# usb2uart_ch340.net
KiCad netlist of a schematic drawn in Altium Designer
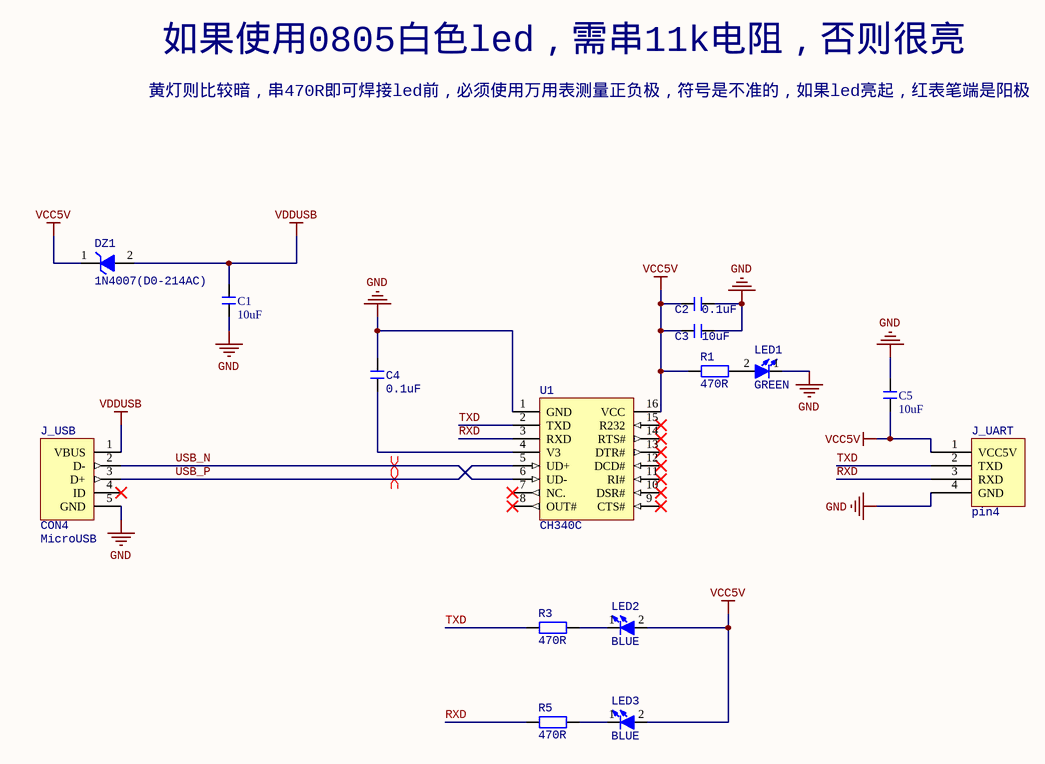
[diagram p0: usb2uart_ch340.SchDoc]

(export (version "E")
  (design (tool "Eeschema 10.0.6"))
  (components
    (comp (ref "C1")
      (value "10uF")
      (footprint "C 0603_M")
      (description "无极性贴片电容")
      (fields (field (name "版权归属") "源创客"))
      (libsource (lib "usb2uart_ch340") (part "C"))
    )
    (comp (ref "C2")
      (value "0.1uF")
      (footprint "C 0402_M")
      (description "无极性贴片电容")
      (fields (field (name "版权归属") "源创客"))
      (libsource (lib "usb2uart_ch340") (part "C"))
    )
    (comp (ref "C3")
      (value "10uF")
      (footprint "C 0603_M")
      (description "无极性贴片电容")
      (fields (field (name "版权归属") "源创客"))
      (libsource (lib "usb2uart_ch340") (part "C"))
    )
    (comp (ref "C4")
      (value "0.1uF")
      (footprint "C 0402_M")
      (description "无极性贴片电容")
      (fields (field (name "版权归属") "源创客"))
      (libsource (lib "usb2uart_ch340") (part "C"))
    )
    (comp (ref "C5")
      (value "10uF")
      (footprint "C 0603_M")
      (description "无极性贴片电容")
      (fields (field (name "版权归属") "源创客"))
      (libsource (lib "usb2uart_ch340") (part "C"))
    )
    (comp (ref "DZ1")
      (value "1N4007(D0-214AC)")
      (footprint "D SMA(DO-214AC)")
      (description "稳压二极管")
      (fields (field (name "版权归属") "源创客"))
      (libsource (lib "Schlib1") (part "DZ"))
    )
    (comp (ref "J_UART")
      (value "pin4")
      (footprint "HDR2.54-LI-4P")
      (libsource (lib "usb2uart_ch340") (part "pin4"))
    )
    (comp (ref "J_USB")
      (value "CON4")
      (footprint "MicroUsb_C404969")
      (libsource (lib "Schlib1") (part "MicroUSB_5P"))
    )
    (comp (ref "LED1")
      (value "GREEN")
      (footprint "D 0805 led")
      (description "贴片LED")
      (fields (field (name "版权归属") "源创客"))
      (libsource (lib "usb2uart_ch340") (part "D LED-SMD"))
    )
    (comp (ref "LED2")
      (value "BLUE")
      (footprint "D 0805 led")
      (description "贴片LED")
      (fields (field (name "版权归属") "源创客"))
      (libsource (lib "usb2uart_ch340") (part "D LED-SMD"))
    )
    (comp (ref "LED3")
      (value "BLUE")
      (footprint "D 0805 led")
      (description "贴片LED")
      (fields (field (name "版权归属") "源创客"))
      (libsource (lib "usb2uart_ch340") (part "D LED-SMD"))
    )
    (comp (ref "R1")
      (value "470R")
      (footprint "R 0603C")
      (description "贴片电阻")
      (libsource (lib "usb2uart_ch340") (part "R"))
    )
    (comp (ref "R3")
      (value "470R")
      (footprint "R 0603C")
      (description "贴片电阻")
      (libsource (lib "usb2uart_ch340") (part "R"))
    )
    (comp (ref "R5")
      (value "470R")
      (footprint "R 0603C")
      (description "贴片电阻")
      (libsource (lib "usb2uart_ch340") (part "R"))
    )
    (comp (ref "U1")
      (value "CH340C")
      (footprint "SOP-16_150mil")
      (description "CH340 是一个 USB 总线的转接芯片，实现 USB 转串口或者 USB 转打印口。")
      (libsource (lib "usb2uart_ch340") (part "CH340C"))
    )
  )
  (nets
    (net (code "1") (name "/RXD") (class "Default")
      (node (ref "J_UART") (pin "3") (pinfunction "RXD_3") (pintype "passive"))
      (node (ref "R5") (pin "1") (pinfunction "1_1") (pintype "passive"))
      (node (ref "U1") (pin "3") (pinfunction "RXD_3") (pintype "passive"))
    )
    (net (code "2") (name "/TXD") (class "Default")
      (node (ref "J_UART") (pin "2") (pinfunction "TXD_2") (pintype "passive"))
      (node (ref "R3") (pin "1") (pinfunction "1_1") (pintype "passive"))
      (node (ref "U1") (pin "2") (pinfunction "TXD_2") (pintype "passive"))
    )
    (net (code "3") (name "/USB_N") (class "Default")
      (node (ref "J_USB") (pin "2") (pinfunction "D-_2") (pintype "output"))
      (node (ref "U1") (pin "6") (pinfunction "UD-_6") (pintype "input"))
    )
    (net (code "4") (name "/USB_P") (class "Default")
      (node (ref "J_USB") (pin "3") (pinfunction "D+_3") (pintype "output"))
      (node (ref "U1") (pin "5") (pinfunction "UD+_5") (pintype "input"))
    )
    (net (code "5") (name "GND") (class "Default")
      (node (ref "C1") (pin "1") (pinfunction "1_1") (pintype "passive"))
      (node (ref "C2") (pin "2") (pinfunction "2_2") (pintype "passive"))
      (node (ref "C3") (pin "2") (pinfunction "2_2") (pintype "passive"))
      (node (ref "C4") (pin "2") (pinfunction "2_2") (pintype "passive"))
      (node (ref "C5") (pin "2") (pinfunction "2_2") (pintype "passive"))
      (node (ref "J_UART") (pin "4") (pinfunction "GND_4") (pintype "passive"))
      (node (ref "J_USB") (pin "5") (pinfunction "GND_5") (pintype "power_in"))
      (node (ref "LED1") (pin "1") (pinfunction "K_1") (pintype "passive"))
      (node (ref "U1") (pin "1") (pinfunction "GND_1") (pintype "power_in"))
    )
    (net (code "6") (name "Net-(LED1-A)") (class "Default")
      (node (ref "LED1") (pin "2") (pinfunction "A_2") (pintype "passive"))
      (node (ref "R1") (pin "2") (pinfunction "2_2") (pintype "passive"))
    )
    (net (code "7") (name "Net-(LED2-K)") (class "Default")
      (node (ref "LED2") (pin "1") (pinfunction "K_1") (pintype "passive"))
      (node (ref "R3") (pin "2") (pinfunction "2_2") (pintype "passive"))
    )
    (net (code "8") (name "Net-(LED3-K)") (class "Default")
      (node (ref "LED3") (pin "1") (pinfunction "K_1") (pintype "passive"))
      (node (ref "R5") (pin "2") (pinfunction "2_2") (pintype "passive"))
    )
    (net (code "9") (name "Net-(U1-V3)") (class "Default")
      (node (ref "C4") (pin "1") (pinfunction "1_1") (pintype "passive"))
      (node (ref "U1") (pin "4") (pinfunction "V3_4") (pintype "power_in"))
    )
    (net (code "10") (name "VCC5V") (class "Default")
      (node (ref "C2") (pin "1") (pinfunction "1_1") (pintype "passive"))
      (node (ref "C3") (pin "1") (pinfunction "1_1") (pintype "passive"))
      (node (ref "C5") (pin "1") (pinfunction "1_1") (pintype "passive"))
      (node (ref "DZ1") (pin "1") (pinfunction "K_1") (pintype "passive"))
      (node (ref "J_UART") (pin "1") (pinfunction "VCC5V_1") (pintype "passive"))
      (node (ref "LED2") (pin "2") (pinfunction "A_2") (pintype "passive"))
      (node (ref "LED3") (pin "2") (pinfunction "A_2") (pintype "passive"))
      (node (ref "R1") (pin "1") (pinfunction "1_1") (pintype "passive"))
      (node (ref "U1") (pin "16") (pinfunction "VCC_16") (pintype "power_in"))
    )
    (net (code "11") (name "VDDUSB") (class "Default")
      (node (ref "C1") (pin "2") (pinfunction "2_2") (pintype "passive"))
      (node (ref "DZ1") (pin "2") (pinfunction "A_2") (pintype "passive"))
      (node (ref "J_USB") (pin "1") (pinfunction "VBUS_1") (pintype "power_in"))
    )
    (net (code "12") (name "unconnected-(J_USB-ID-Pad4)") (class "Default")
      (node (ref "J_USB") (pin "4") (pinfunction "ID_4") (pintype "passive+no_connect"))
    )
    (net (code "13") (name "unconnected-(U1-CTS#-Pad9)") (class "Default")
      (node (ref "U1") (pin "9") (pinfunction "CTS#_9") (pintype "input+no_connect"))
    )
    (net (code "14") (name "unconnected-(U1-DCD#-Pad12)") (class "Default")
      (node (ref "U1") (pin "12") (pinfunction "DCD#_12") (pintype "input+no_connect"))
    )
    (net (code "15") (name "unconnected-(U1-DSR#-Pad10)") (class "Default")
      (node (ref "U1") (pin "10") (pinfunction "DSR#_10") (pintype "input+no_connect"))
    )
    (net (code "16") (name "unconnected-(U1-DTR#-Pad13)") (class "Default")
      (node (ref "U1") (pin "13") (pinfunction "DTR#_13") (pintype "output+no_connect"))
    )
    (net (code "17") (name "unconnected-(U1-NC.-Pad7)") (class "Default")
      (node (ref "U1") (pin "7") (pinfunction "NC._7") (pintype "output+no_connect"))
    )
    (net (code "18") (name "unconnected-(U1-OUT#-Pad8)") (class "Default")
      (node (ref "U1") (pin "8") (pinfunction "OUT#_8") (pintype "output+no_connect"))
    )
    (net (code "19") (name "unconnected-(U1-R232-Pad15)") (class "Default")
      (node (ref "U1") (pin "15") (pinfunction "R232_15") (pintype "input+no_connect"))
    )
    (net (code "20") (name "unconnected-(U1-RI#-Pad11)") (class "Default")
      (node (ref "U1") (pin "11") (pinfunction "RI#_11") (pintype "input+no_connect"))
    )
    (net (code "21") (name "unconnected-(U1-RTS#-Pad14)") (class "Default")
      (node (ref "U1") (pin "14") (pinfunction "RTS#_14") (pintype "output+no_connect"))
    )
  )
)
